# mayfly_peripheral_breakout.net
KiCad netlist of a schematic drawn in EAGLE
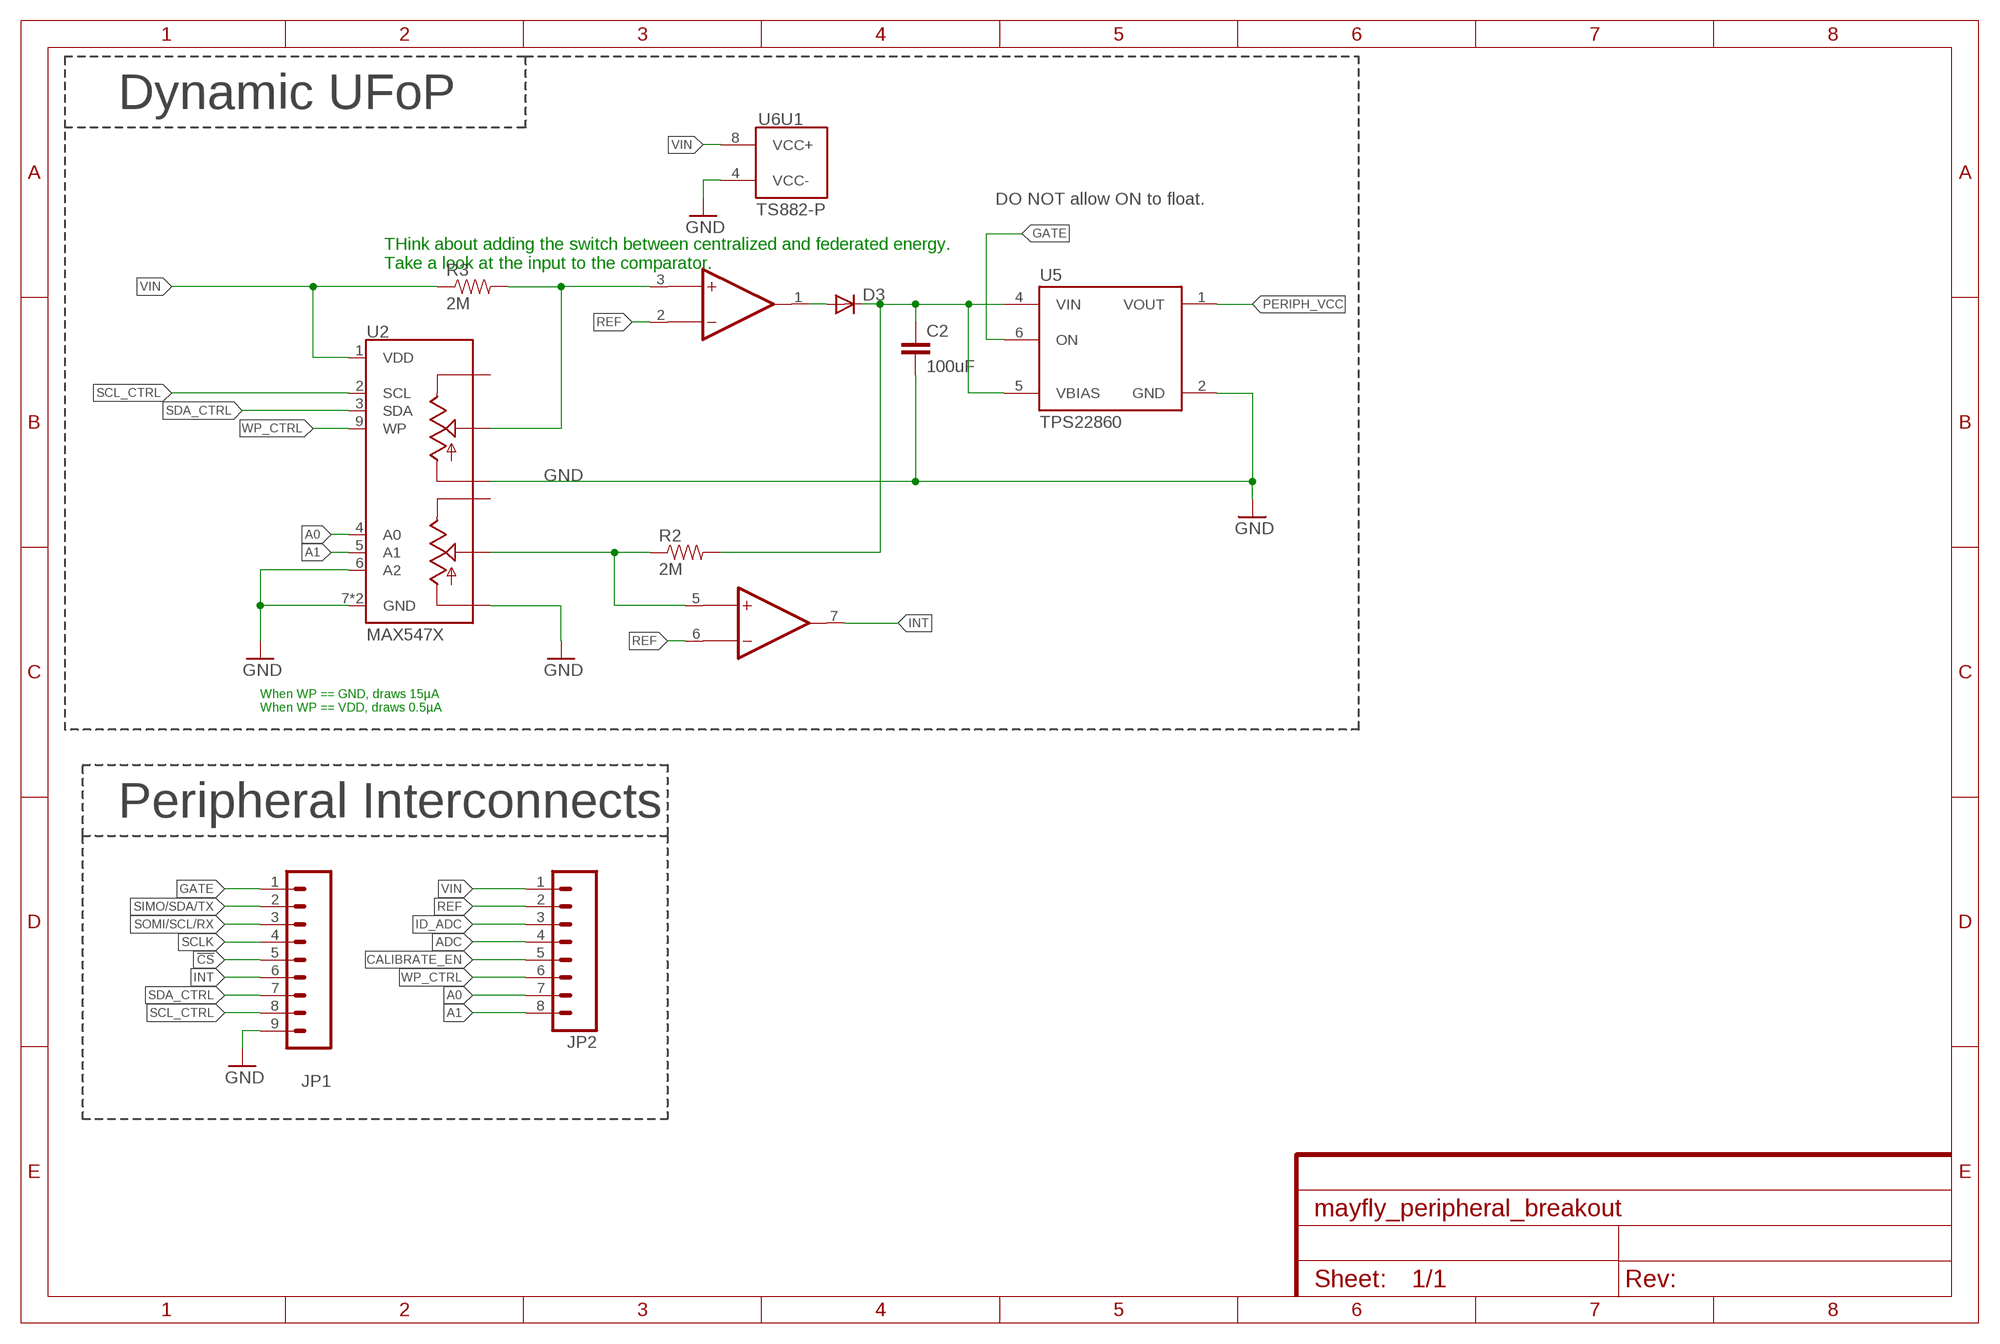
[diagram p0: schematic, sheet 1]

(export (version "E")
  (design (tool "Eeschema 10.0.6"))
  (components
    (comp (ref "C2")
      (value "100uF")
      (footprint "eagle-import:1210")
      (libsource (lib "eagle-import") (part "CAP1210"))
    )
    (comp (ref "D3")
      (value "DIODESOD")
      (footprint "eagle-import:SOD-323")
      (libsource (lib "eagle-import") (part "DIODESOD"))
    )
    (comp (ref "JP1")
      (value "M09LOCK")
      (footprint "eagle-import:1X09_LOCK")
      (libsource (lib "eagle-import") (part "M09LOCK"))
    )
    (comp (ref "JP2")
      (value "M08LOCK")
      (footprint "eagle-import:1X08_LOCK")
      (libsource (lib "eagle-import") (part "M08LOCK"))
    )
    (comp (ref "R2")
      (value "2M")
      (footprint "eagle-import:0603")
      (libsource (lib "eagle-import") (part "R-EU0603"))
    )
    (comp (ref "R3")
      (value "2M")
      (footprint "eagle-import:0603")
      (libsource (lib "eagle-import") (part "R-EU0603"))
    )
    (comp (ref "U2")
      (value "MAX547X")
      (footprint "eagle-import:QFN16")
      (libsource (lib "eagle-import") (part "MAX547X"))
    )
    (comp (ref "U5")
      (value "TPS22860")
      (footprint "eagle-import:TSOT23-6")
      (libsource (lib "eagle-import") (part "TPS22860"))
    )
    (comp (ref "U6")
      (value "TS882-P")
      (footprint "eagle-import:UDFN8")
      (fields (field (name "DIGIKEY") "497-14073-1-ND"))
      (libsource (lib "eagle-import") (part "TS882-P"))
    )
  )
  (nets
    (net (code "1") (name "/~{CS}") (class "Default")
      (node (ref "JP1") (pin "5") (pinfunction "5_5") (pintype "passive"))
    )
    (net (code "2") (name "A0") (class "Default")
      (node (ref "JP2") (pin "7") (pinfunction "7_7") (pintype "passive"))
      (node (ref "U2") (pin "4") (pinfunction "A0_4") (pintype "bidirectional"))
    )
    (net (code "3") (name "A1") (class "Default")
      (node (ref "JP2") (pin "8") (pinfunction "8_8") (pintype "passive"))
      (node (ref "U2") (pin "5") (pinfunction "A1_5") (pintype "bidirectional"))
    )
    (net (code "4") (name "ADC") (class "Default")
      (node (ref "JP2") (pin "4") (pinfunction "4_4") (pintype "passive"))
    )
    (net (code "5") (name "CALIBRATE_EN") (class "Default")
      (node (ref "JP2") (pin "5") (pinfunction "5_5") (pintype "passive"))
    )
    (net (code "6") (name "GATE") (class "Default")
      (node (ref "JP1") (pin "1") (pinfunction "1_1") (pintype "passive"))
      (node (ref "U5") (pin "6") (pinfunction "ON_6") (pintype "bidirectional"))
    )
    (net (code "7") (name "GND") (class "Default")
      (node (ref "C2") (pin "2") (pinfunction "2_2") (pintype "passive"))
      (node (ref "JP1") (pin "9") (pinfunction "9_9") (pintype "passive"))
      (node (ref "U2") (pin "10") (pinfunction "LB_10") (pintype "bidirectional"))
      (node (ref "U2") (pin "13") (pinfunction "LA_13") (pintype "passive"))
      (node (ref "U2") (pin "6") (pinfunction "A2_6") (pintype "bidirectional"))
      (node (ref "U2") (pin "7") (pinfunction "GND_7") (pintype "bidirectional"))
      (node (ref "U2") (pin "TH") (pinfunction "GND_TH") (pintype "bidirectional"))
      (node (ref "U5") (pin "2") (pinfunction "GND_2") (pintype "bidirectional"))
      (node (ref "U6") (pin "4") (pinfunction "VCC-_4") (pintype "bidirectional"))
    )
    (net (code "8") (name "ID_ADC") (class "Default")
      (node (ref "JP2") (pin "3") (pinfunction "3_3") (pintype "passive"))
    )
    (net (code "9") (name "INT") (class "Default")
      (node (ref "JP1") (pin "6") (pinfunction "6_6") (pintype "passive"))
      (node (ref "U6") (pin "7") (pinfunction "OUT1_7") (pintype "output"))
    )
    (net (code "10") (name "Net-(D3-A)") (class "Default")
      (node (ref "D3") (pin "2") (pinfunction "A_2") (pintype "passive"))
      (node (ref "U6") (pin "1") (pinfunction "OUT1_1") (pintype "output"))
    )
    (net (code "11") (name "Net-(D3-C)") (class "Default")
      (node (ref "C2") (pin "1") (pinfunction "1_1") (pintype "passive"))
      (node (ref "D3") (pin "1") (pinfunction "C_1") (pintype "passive"))
      (node (ref "R2") (pin "2") (pinfunction "2_2") (pintype "passive"))
      (node (ref "U5") (pin "4") (pinfunction "VIN_4") (pintype "bidirectional"))
      (node (ref "U5") (pin "5") (pinfunction "VBIAS_5") (pintype "bidirectional"))
    )
    (net (code "12") (name "Net-(U2-WA)") (class "Default")
      (node (ref "R3") (pin "2") (pinfunction "2_2") (pintype "passive"))
      (node (ref "U2") (pin "14") (pinfunction "WA_14") (pintype "passive"))
      (node (ref "U6") (pin "3") (pinfunction "IN1+_3") (pintype "input"))
    )
    (net (code "13") (name "Net-(U2-WB)") (class "Default")
      (node (ref "R2") (pin "1") (pinfunction "1_1") (pintype "passive"))
      (node (ref "U2") (pin "11") (pinfunction "WB_11") (pintype "bidirectional"))
      (node (ref "U6") (pin "5") (pinfunction "IN1+_5") (pintype "input"))
    )
    (net (code "14") (name "PERIPH_VCC") (class "Default")
      (node (ref "U5") (pin "1") (pinfunction "VOUT_1") (pintype "bidirectional"))
    )
    (net (code "15") (name "REF") (class "Default")
      (node (ref "JP2") (pin "2") (pinfunction "2_2") (pintype "passive"))
      (node (ref "U6") (pin "2") (pinfunction "IN1-_2") (pintype "input"))
      (node (ref "U6") (pin "6") (pinfunction "IN1-_6") (pintype "input"))
    )
    (net (code "16") (name "SCLK") (class "Default")
      (node (ref "JP1") (pin "4") (pinfunction "4_4") (pintype "passive"))
    )
    (net (code "17") (name "SCL_CTRL") (class "Default")
      (node (ref "JP1") (pin "8") (pinfunction "8_8") (pintype "passive"))
      (node (ref "U2") (pin "2") (pinfunction "SCL_2") (pintype "bidirectional"))
    )
    (net (code "18") (name "SDA_CTRL") (class "Default")
      (node (ref "JP1") (pin "7") (pinfunction "7_7") (pintype "passive"))
      (node (ref "U2") (pin "3") (pinfunction "SDA_3") (pintype "bidirectional"))
    )
    (net (code "19") (name "SIMO{slash}SDA{slash}TX") (class "Default")
      (node (ref "JP1") (pin "2") (pinfunction "2_2") (pintype "passive"))
    )
    (net (code "20") (name "SOMI{slash}SCL{slash}RX") (class "Default")
      (node (ref "JP1") (pin "3") (pinfunction "3_3") (pintype "passive"))
    )
    (net (code "21") (name "VIN") (class "Default")
      (node (ref "JP2") (pin "1") (pinfunction "1_1") (pintype "passive"))
      (node (ref "R3") (pin "1") (pinfunction "1_1") (pintype "passive"))
      (node (ref "U2") (pin "1") (pinfunction "VDD_1") (pintype "bidirectional"))
      (node (ref "U6") (pin "8") (pinfunction "VCC+_8") (pintype "bidirectional"))
    )
    (net (code "22") (name "WP_CTRL") (class "Default")
      (node (ref "JP2") (pin "6") (pinfunction "6_6") (pintype "passive"))
      (node (ref "U2") (pin "9") (pinfunction "WP_9") (pintype "bidirectional"))
    )
    (net (code "23") (name "unconnected-(U2-HA-Pad15)") (class "Default")
      (node (ref "U2") (pin "15") (pinfunction "HA_15") (pintype "passive"))
    )
    (net (code "24") (name "unconnected-(U2-HB-Pad12)") (class "Default")
      (node (ref "U2") (pin "12") (pinfunction "HB_12") (pintype "bidirectional"))
    )
  )
)
